# I2CSDCardModule.net
KiCad netlist of a schematic drawn in EAGLE
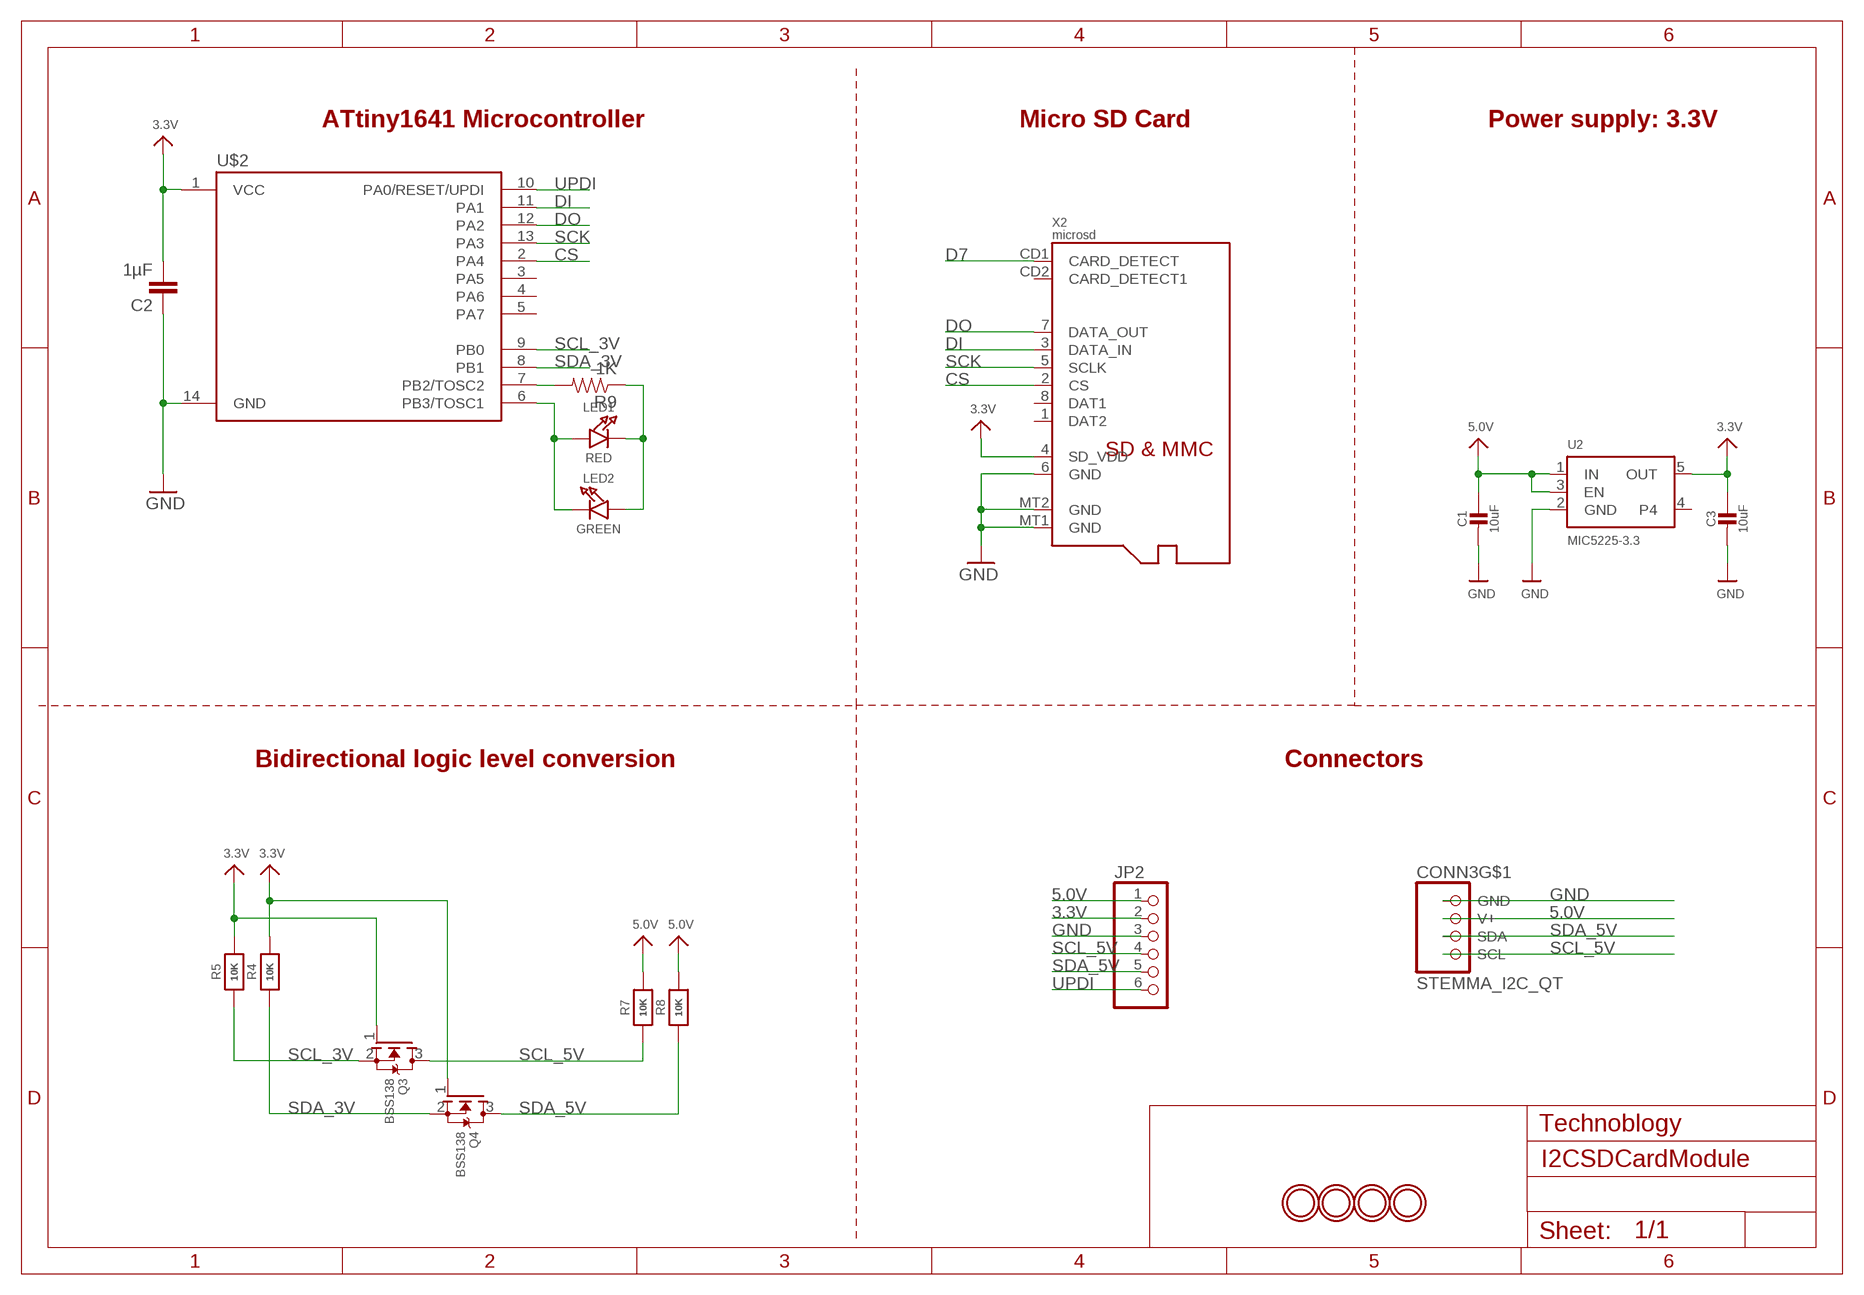
[diagram p0: schematic, sheet 1]

(export (version "E")
  (design (tool "Eeschema 10.0.6"))
  (components
    (comp (ref "C1")
      (value "10uF")
      (footprint "eagle-import:0805-NO")
      (libsource (lib "eagle-import") (part "CAP_CERAMIC0805-NOOUTLINE"))
    )
    (comp (ref "C2")
      (value "1µF")
      (footprint "eagle-import:0805")
      (libsource (lib "eagle-import") (part "CAP0805"))
    )
    (comp (ref "C3")
      (value "10uF")
      (footprint "eagle-import:0805-NO")
      (libsource (lib "eagle-import") (part "CAP_CERAMIC0805-NOOUTLINE"))
    )
    (comp (ref "CONN3")
      (value "STEMMA_I2C_QT")
      (footprint "eagle-import:JST_SH4")
      (libsource (lib "eagle-import") (part "STEMMA_I2C_QT"))
    )
    (comp (ref "JP2")
      (value "HEADER-1X6ROUND")
      (footprint "eagle-import:1X06_ROUND")
      (libsource (lib "eagle-import") (part "HEADER-1X6ROUND"))
    )
    (comp (ref "LED1")
      (value "RED")
      (footprint "eagle-import:CHIPLED_0805_NOOUTLINE")
      (libsource (lib "eagle-import") (part "LED0805_NOOUTLINE"))
    )
    (comp (ref "LED2")
      (value "GREEN")
      (footprint "eagle-import:CHIPLED_0805_NOOUTLINE")
      (libsource (lib "eagle-import") (part "LED0805_NOOUTLINE"))
    )
    (comp (ref "Q3")
      (value "BSS138")
      (footprint "eagle-import:SOT23-WIDE")
      (libsource (lib "eagle-import") (part "MOSFET-NWIDE"))
    )
    (comp (ref "Q4")
      (value "BSS138")
      (footprint "eagle-import:SOT23-WIDE")
      (libsource (lib "eagle-import") (part "MOSFET-NWIDE"))
    )
    (comp (ref "R4")
      (value "10K")
      (footprint "eagle-import:0805-NO")
      (libsource (lib "eagle-import") (part "RESISTOR0805_NOOUTLINE"))
    )
    (comp (ref "R5")
      (value "10K")
      (footprint "eagle-import:0805-NO")
      (libsource (lib "eagle-import") (part "RESISTOR0805_NOOUTLINE"))
    )
    (comp (ref "R7")
      (value "10K")
      (footprint "eagle-import:0805-NO")
      (libsource (lib "eagle-import") (part "RESISTOR0805_NOOUTLINE"))
    )
    (comp (ref "R8")
      (value "10K")
      (footprint "eagle-import:0805-NO")
      (libsource (lib "eagle-import") (part "RESISTOR0805_NOOUTLINE"))
    )
    (comp (ref "R9")
      (value "1K")
      (footprint "eagle-import:0805")
      (libsource (lib "eagle-import") (part "0.3OHM-1/8W-1%(0805)"))
    )
    (comp (ref "U$1")
      (value "MOUNTINGHOLE2.5")
      (footprint "eagle-import:MOUNTINGHOLE_2.5_PLATED")
      (libsource (lib "eagle-import") (part "MOUNTINGHOLE2.5"))
    )
    (comp (ref "U$2")
      (value "ATTINY414")
      (footprint "eagle-import:SO14")
      (libsource (lib "eagle-import") (part "ATTINY414"))
    )
    (comp (ref "U$5")
      (value "MOUNTINGHOLE2.5")
      (footprint "eagle-import:MOUNTINGHOLE_2.5_PLATED")
      (libsource (lib "eagle-import") (part "MOUNTINGHOLE2.5"))
    )
    (comp (ref "U$6")
      (value "MOUNTINGHOLE2.5")
      (footprint "eagle-import:MOUNTINGHOLE_2.5_PLATED")
      (libsource (lib "eagle-import") (part "MOUNTINGHOLE2.5"))
    )
    (comp (ref "U$9")
      (value "MOUNTINGHOLE2.5")
      (footprint "eagle-import:MOUNTINGHOLE_2.5_PLATED")
      (libsource (lib "eagle-import") (part "MOUNTINGHOLE2.5"))
    )
    (comp (ref "U2")
      (value "MIC5225-3.3")
      (footprint "eagle-import:SOT23-5")
      (libsource (lib "eagle-import") (part "VREG_SOT23-5"))
    )
    (comp (ref "X2")
      (value "microsd")
      (footprint "eagle-import:MICROSD")
      (libsource (lib "eagle-import") (part "MICROSD"))
    )
  )
  (nets
    (net (code "1") (name "/CS") (class "Default")
      (node (ref "U$2") (pin "2") (pinfunction "PA4_2") (pintype "bidirectional"))
      (node (ref "X2") (pin "2") (pinfunction "CS_2") (pintype "input"))
    )
    (net (code "2") (name "/D7") (class "Default")
      (node (ref "X2") (pin "CD1") (pinfunction "CARD_DETECT_CD1") (pintype "passive"))
    )
    (net (code "3") (name "/DI") (class "Default")
      (node (ref "U$2") (pin "11") (pinfunction "PA1_11") (pintype "bidirectional"))
      (node (ref "X2") (pin "3") (pinfunction "DATA_IN_3") (pintype "input"))
    )
    (net (code "4") (name "/DO") (class "Default")
      (node (ref "U$2") (pin "12") (pinfunction "PA2_12") (pintype "bidirectional"))
      (node (ref "X2") (pin "7") (pinfunction "DATA_OUT_7") (pintype "output"))
    )
    (net (code "5") (name "/SCK") (class "Default")
      (node (ref "U$2") (pin "13") (pinfunction "PA3_13") (pintype "bidirectional"))
      (node (ref "X2") (pin "5") (pinfunction "SCLK_5") (pintype "input"))
    )
    (net (code "6") (name "/SCL_3V") (class "Default")
      (node (ref "Q3") (pin "2") (pinfunction "S_2") (pintype "bidirectional"))
      (node (ref "R5") (pin "1") (pinfunction "1_1") (pintype "passive"))
      (node (ref "U$2") (pin "9") (pinfunction "PB0_9") (pintype "bidirectional"))
    )
    (net (code "7") (name "/SCL_5V") (class "Default")
      (node (ref "CONN3") (pin "4") (pinfunction "SCL_4") (pintype "passive"))
      (node (ref "JP2") (pin "4") (pinfunction "4_4") (pintype "passive"))
      (node (ref "Q3") (pin "3") (pinfunction "D_3") (pintype "bidirectional"))
      (node (ref "R7") (pin "1") (pinfunction "1_1") (pintype "passive"))
    )
    (net (code "8") (name "/SDA_3V") (class "Default")
      (node (ref "Q4") (pin "2") (pinfunction "S_2") (pintype "bidirectional"))
      (node (ref "R4") (pin "1") (pinfunction "1_1") (pintype "passive"))
      (node (ref "U$2") (pin "8") (pinfunction "PB1_8") (pintype "bidirectional"))
    )
    (net (code "9") (name "/SDA_5V") (class "Default")
      (node (ref "CONN3") (pin "3") (pinfunction "SDA_3") (pintype "passive"))
      (node (ref "JP2") (pin "5") (pinfunction "5_5") (pintype "passive"))
      (node (ref "Q4") (pin "3") (pinfunction "D_3") (pintype "bidirectional"))
      (node (ref "R8") (pin "1") (pinfunction "1_1") (pintype "passive"))
    )
    (net (code "10") (name "/UPDI") (class "Default")
      (node (ref "JP2") (pin "6") (pinfunction "6_6") (pintype "passive"))
      (node (ref "U$2") (pin "10") (pinfunction "PA0/RESET/UPDI_10") (pintype "bidirectional"))
    )
    (net (code "11") (name "3.3V") (class "Default")
      (node (ref "C2") (pin "2") (pinfunction "2_2") (pintype "passive"))
      (node (ref "C3") (pin "1") (pinfunction "1_1") (pintype "passive"))
      (node (ref "JP2") (pin "2") (pinfunction "2_2") (pintype "passive"))
      (node (ref "Q3") (pin "1") (pinfunction "G_1") (pintype "bidirectional"))
      (node (ref "Q4") (pin "1") (pinfunction "G_1") (pintype "bidirectional"))
      (node (ref "R4") (pin "2") (pinfunction "2_2") (pintype "passive"))
      (node (ref "R5") (pin "2") (pinfunction "2_2") (pintype "passive"))
      (node (ref "U$2") (pin "1") (pinfunction "VCC_1") (pintype "bidirectional"))
      (node (ref "U2") (pin "5") (pinfunction "OUT_5") (pintype "power_in"))
      (node (ref "X2") (pin "4") (pinfunction "SD_VDD_4") (pintype "power_in"))
    )
    (net (code "12") (name "5.0V") (class "Default")
      (node (ref "C1") (pin "1") (pinfunction "1_1") (pintype "passive"))
      (node (ref "CONN3") (pin "2") (pinfunction "V+_2") (pintype "passive"))
      (node (ref "JP2") (pin "1") (pinfunction "1_1") (pintype "passive"))
      (node (ref "R7") (pin "2") (pinfunction "2_2") (pintype "passive"))
      (node (ref "R8") (pin "2") (pinfunction "2_2") (pintype "passive"))
      (node (ref "U2") (pin "1") (pinfunction "IN_1") (pintype "power_in"))
      (node (ref "U2") (pin "3") (pinfunction "EN_3") (pintype "input"))
    )
    (net (code "13") (name "GND") (class "Default")
      (node (ref "C1") (pin "2") (pinfunction "2_2") (pintype "passive"))
      (node (ref "C2") (pin "1") (pinfunction "1_1") (pintype "passive"))
      (node (ref "C3") (pin "2") (pinfunction "2_2") (pintype "passive"))
      (node (ref "CONN3") (pin "1") (pinfunction "GND_1") (pintype "passive"))
      (node (ref "JP2") (pin "3") (pinfunction "3_3") (pintype "passive"))
      (node (ref "U$2") (pin "14") (pinfunction "GND_14") (pintype "bidirectional"))
      (node (ref "U2") (pin "2") (pinfunction "GND_2") (pintype "power_in"))
      (node (ref "X2") (pin "6") (pinfunction "GND_6") (pintype "power_in"))
      (node (ref "X2") (pin "MT1") (pinfunction "GND_MT1") (pintype "power_in"))
      (node (ref "X2") (pin "MT2") (pinfunction "GND_MT2") (pintype "power_in"))
    )
    (net (code "14") (name "Net-(LED1-PadC)") (class "Default")
      (node (ref "LED1") (pin "C") (pinfunction "C_C") (pintype "passive"))
      (node (ref "LED2") (pin "A") (pinfunction "A_A") (pintype "passive"))
      (node (ref "R9") (pin "1") (pinfunction "1_1") (pintype "passive"))
    )
    (net (code "15") (name "Net-(U$2-PB2{slash}TOSC2)") (class "Default")
      (node (ref "R9") (pin "2") (pinfunction "2_2") (pintype "passive"))
      (node (ref "U$2") (pin "7") (pinfunction "PB2/TOSC2_7") (pintype "bidirectional"))
    )
    (net (code "16") (name "Net-(U$2-PB3{slash}TOSC1)") (class "Default")
      (node (ref "LED1") (pin "A") (pinfunction "A_A") (pintype "passive"))
      (node (ref "LED2") (pin "C") (pinfunction "C_C") (pintype "passive"))
      (node (ref "U$2") (pin "6") (pinfunction "PB3/TOSC1_6") (pintype "bidirectional"))
    )
    (net (code "17") (name "unconnected-(U$2-PA5-Pad3)") (class "Default")
      (node (ref "U$2") (pin "3") (pinfunction "PA5_3") (pintype "bidirectional"))
    )
    (net (code "18") (name "unconnected-(U$2-PA6-Pad4)") (class "Default")
      (node (ref "U$2") (pin "4") (pinfunction "PA6_4") (pintype "bidirectional"))
    )
    (net (code "19") (name "unconnected-(U$2-PA7-Pad5)") (class "Default")
      (node (ref "U$2") (pin "5") (pinfunction "PA7_5") (pintype "bidirectional"))
    )
    (net (code "20") (name "unconnected-(U2-P4-Pad4)") (class "Default")
      (node (ref "U2") (pin "4") (pinfunction "P4_4") (pintype "bidirectional"))
    )
    (net (code "21") (name "unconnected-(X2-CARD_DETECT1-PadCD2)") (class "Default")
      (node (ref "X2") (pin "CD2") (pinfunction "CARD_DETECT1_CD2") (pintype "passive"))
    )
    (net (code "22") (name "unconnected-(X2-DAT1-Pad8)") (class "Default")
      (node (ref "X2") (pin "8") (pinfunction "DAT1_8") (pintype "bidirectional"))
    )
    (net (code "23") (name "unconnected-(X2-DAT2-Pad1)") (class "Default")
      (node (ref "X2") (pin "1") (pinfunction "DAT2_1") (pintype "bidirectional"))
    )
  )
)
